# BSK3.net
KiCad netlist of a schematic drawn in EAGLE
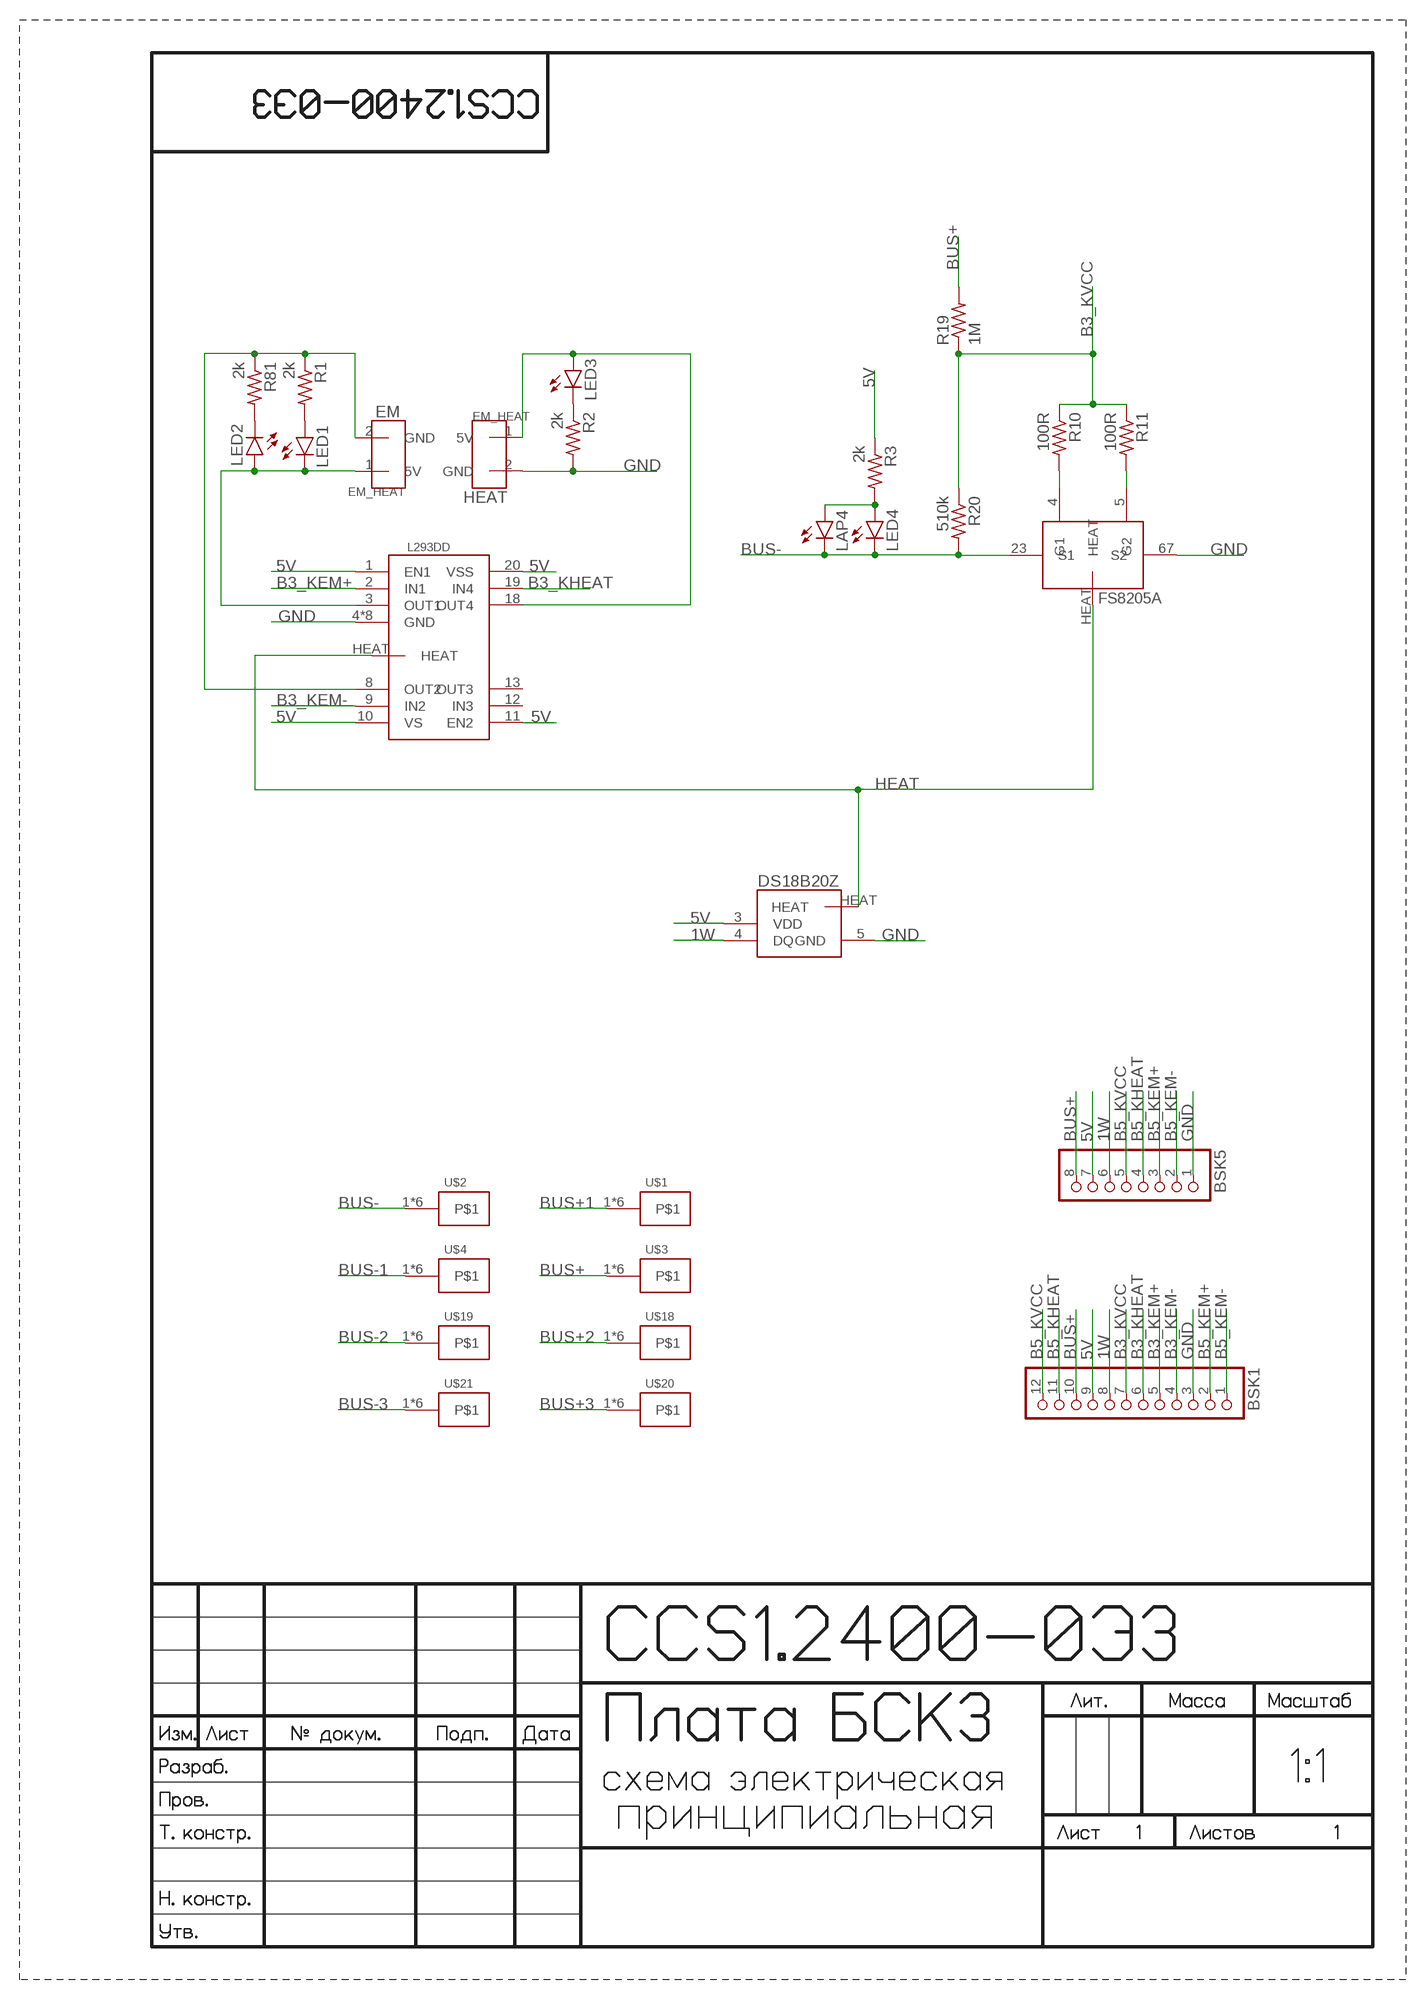
[diagram p0: schematic, sheet 1]

(export (version "E")
  (design (tool "Eeschema 10.0.6"))
  (components
    (comp (ref "BSK1")
      (value "PINHD-1X12")
      (footprint "eagle-import:1X12")
      (libsource (lib "eagle-import") (part "PINHD-1X12"))
    )
    (comp (ref "BSK5")
      (value "PINHD-1X8")
      (footprint "eagle-import:1X08")
      (libsource (lib "eagle-import") (part "PINHD-1X8"))
    )
    (comp (ref "DS18B20Z")
      (value "DS18B20Z")
      (footprint "eagle-import:DS18B20Z")
      (libsource (lib "eagle-import") (part "DS18B20Z"))
    )
    (comp (ref "FS8205A")
      (value "FS8205A+")
      (footprint "eagle-import:FS8205A+")
      (libsource (lib "eagle-import") (part "FS8205A+"))
    )
    (comp (ref "L293DD")
      (value "L293DD")
      (footprint "eagle-import:L293DD")
      (libsource (lib "eagle-import") (part "L293DD"))
    )
    (comp (ref "LAP4")
      (value "LAP4-BOTTOM")
      (footprint "eagle-import:P47F-BOTTOM")
      (libsource (lib "eagle-import") (part "P4-BOTTOMLA"))
    )
    (comp (ref "LED1")
      (value "LEDCHIPLED_0603")
      (footprint "eagle-import:CHIPLED_0603")
      (libsource (lib "eagle-import") (part "LEDCHIPLED_0603"))
    )
    (comp (ref "LED2")
      (value "LEDCHIPLED_0603")
      (footprint "eagle-import:CHIPLED_0603")
      (libsource (lib "eagle-import") (part "LEDCHIPLED_0603"))
    )
    (comp (ref "LED3")
      (value "LEDCHIPLED_0603")
      (footprint "eagle-import:CHIPLED_0603")
      (libsource (lib "eagle-import") (part "LEDCHIPLED_0603"))
    )
    (comp (ref "LED4")
      (value "LEDCHIPLED_0603")
      (footprint "eagle-import:CHIPLED_0603")
      (libsource (lib "eagle-import") (part "LEDCHIPLED_0603"))
    )
    (comp (ref "R1")
      (value "2k")
      (footprint "eagle-import:R0603")
      (libsource (lib "eagle-import") (part "R-US_R0603"))
    )
    (comp (ref "R2")
      (value "2k")
      (footprint "eagle-import:R0603")
      (libsource (lib "eagle-import") (part "R-US_R0603"))
    )
    (comp (ref "R3")
      (value "2k")
      (footprint "eagle-import:R0603")
      (libsource (lib "eagle-import") (part "R-US_R0603"))
    )
    (comp (ref "R10")
      (value "100R")
      (footprint "eagle-import:R0603")
      (libsource (lib "eagle-import") (part "R-US_R0603"))
    )
    (comp (ref "R11")
      (value "100R")
      (footprint "eagle-import:R0603")
      (libsource (lib "eagle-import") (part "R-US_R0603"))
    )
    (comp (ref "R19")
      (value "1M")
      (footprint "eagle-import:R0603")
      (libsource (lib "eagle-import") (part "R-US_R0603"))
    )
    (comp (ref "R20")
      (value "510k")
      (footprint "eagle-import:R0603")
      (libsource (lib "eagle-import") (part "R-US_R0603"))
    )
    (comp (ref "R81")
      (value "2k")
      (footprint "eagle-import:R0603")
      (libsource (lib "eagle-import") (part "R-US_R0603"))
    )
    (comp (ref "U$1")
      (value "KCONNECT")
      (footprint "eagle-import:KCONNECT")
      (libsource (lib "eagle-import") (part "KCONNECT"))
    )
    (comp (ref "U$2")
      (value "KCONNECT")
      (footprint "eagle-import:KCONNECT")
      (libsource (lib "eagle-import") (part "KCONNECT"))
    )
    (comp (ref "U$3")
      (value "KCONNECT")
      (footprint "eagle-import:KCONNECT")
      (libsource (lib "eagle-import") (part "KCONNECT"))
    )
    (comp (ref "U$4")
      (value "KCONNECT")
      (footprint "eagle-import:KCONNECT")
      (libsource (lib "eagle-import") (part "KCONNECT"))
    )
    (comp (ref "U$6")
      (value "EM_HEAT")
      (footprint "eagle-import:EM_HEAT")
      (libsource (lib "eagle-import") (part "EM_HEAT"))
    )
    (comp (ref "U$7")
      (value "EM_HEAT")
      (footprint "eagle-import:EM_HEAT")
      (libsource (lib "eagle-import") (part "EM_HEAT"))
    )
    (comp (ref "U$18")
      (value "KCONNECT")
      (footprint "eagle-import:KCONNECT")
      (libsource (lib "eagle-import") (part "KCONNECT"))
    )
    (comp (ref "U$19")
      (value "KCONNECT")
      (footprint "eagle-import:KCONNECT")
      (libsource (lib "eagle-import") (part "KCONNECT"))
    )
    (comp (ref "U$20")
      (value "KCONNECT")
      (footprint "eagle-import:KCONNECT")
      (libsource (lib "eagle-import") (part "KCONNECT"))
    )
    (comp (ref "U$21")
      (value "KCONNECT")
      (footprint "eagle-import:KCONNECT")
      (libsource (lib "eagle-import") (part "KCONNECT"))
    )
  )
  (nets
    (net (code "1") (name "/1W") (class "Default")
      (node (ref "BSK1") (pin "8") (pinfunction "8_8") (pintype "passive"))
      (node (ref "BSK5") (pin "6") (pinfunction "6_6") (pintype "passive"))
      (node (ref "DS18B20Z") (pin "4") (pinfunction "DQ_4") (pintype "bidirectional"))
    )
    (net (code "2") (name "/5V") (class "Default")
      (node (ref "BSK1") (pin "9") (pinfunction "9_9") (pintype "passive"))
      (node (ref "BSK5") (pin "7") (pinfunction "7_7") (pintype "passive"))
      (node (ref "DS18B20Z") (pin "3") (pinfunction "VDD_3") (pintype "bidirectional"))
      (node (ref "L293DD") (pin "1") (pinfunction "EN1_1") (pintype "bidirectional"))
      (node (ref "L293DD") (pin "10") (pinfunction "VS_10") (pintype "bidirectional"))
      (node (ref "L293DD") (pin "11") (pinfunction "EN2_11") (pintype "bidirectional"))
      (node (ref "L293DD") (pin "20") (pinfunction "VSS_20") (pintype "bidirectional"))
      (node (ref "R3") (pin "1") (pinfunction "1_1") (pintype "passive"))
    )
    (net (code "3") (name "/B3_KEM+") (class "Default")
      (node (ref "BSK1") (pin "5") (pinfunction "5_5") (pintype "passive"))
      (node (ref "L293DD") (pin "2") (pinfunction "IN1_2") (pintype "bidirectional"))
    )
    (net (code "4") (name "/B3_KEM-") (class "Default")
      (node (ref "BSK1") (pin "4") (pinfunction "4_4") (pintype "passive"))
      (node (ref "L293DD") (pin "9") (pinfunction "IN2_9") (pintype "bidirectional"))
    )
    (net (code "5") (name "/B3_KHEAT") (class "Default")
      (node (ref "BSK1") (pin "6") (pinfunction "6_6") (pintype "passive"))
      (node (ref "L293DD") (pin "19") (pinfunction "IN4_19") (pintype "bidirectional"))
    )
    (net (code "6") (name "/B3_KVCC") (class "Default")
      (node (ref "BSK1") (pin "7") (pinfunction "7_7") (pintype "passive"))
      (node (ref "R10") (pin "1") (pinfunction "1_1") (pintype "passive"))
      (node (ref "R11") (pin "1") (pinfunction "1_1") (pintype "passive"))
      (node (ref "R19") (pin "1") (pinfunction "1_1") (pintype "passive"))
      (node (ref "R20") (pin "1") (pinfunction "1_1") (pintype "passive"))
    )
    (net (code "7") (name "/B5_KEM+") (class "Default")
      (node (ref "BSK1") (pin "2") (pinfunction "2_2") (pintype "passive"))
      (node (ref "BSK5") (pin "3") (pinfunction "3_3") (pintype "passive"))
    )
    (net (code "8") (name "/B5_KEM-") (class "Default")
      (node (ref "BSK1") (pin "1") (pinfunction "1_1") (pintype "passive"))
      (node (ref "BSK5") (pin "2") (pinfunction "2_2") (pintype "passive"))
    )
    (net (code "9") (name "/B5_KHEAT") (class "Default")
      (node (ref "BSK1") (pin "11") (pinfunction "11_11") (pintype "passive"))
      (node (ref "BSK5") (pin "4") (pinfunction "4_4") (pintype "passive"))
    )
    (net (code "10") (name "/B5_KVCC") (class "Default")
      (node (ref "BSK1") (pin "12") (pinfunction "12_12") (pintype "passive"))
      (node (ref "BSK5") (pin "5") (pinfunction "5_5") (pintype "passive"))
    )
    (net (code "11") (name "/BUS+") (class "Default")
      (node (ref "BSK1") (pin "10") (pinfunction "10_10") (pintype "passive"))
      (node (ref "BSK5") (pin "8") (pinfunction "8_8") (pintype "passive"))
      (node (ref "R19") (pin "2") (pinfunction "2_2") (pintype "passive"))
      (node (ref "U$3") (pin "1") (pinfunction "P$1_1") (pintype "bidirectional"))
      (node (ref "U$3") (pin "2") (pinfunction "P$1_2") (pintype "bidirectional"))
      (node (ref "U$3") (pin "3") (pinfunction "P$1_3") (pintype "bidirectional"))
      (node (ref "U$3") (pin "4") (pinfunction "P$1_4") (pintype "bidirectional"))
      (node (ref "U$3") (pin "P$1") (pinfunction "P$1_P$1") (pintype "bidirectional"))
      (node (ref "U$3") (pin "P$2") (pinfunction "P$1_P$2") (pintype "bidirectional"))
    )
    (net (code "12") (name "/BUS+1") (class "Default")
      (node (ref "U$1") (pin "1") (pinfunction "P$1_1") (pintype "bidirectional"))
      (node (ref "U$1") (pin "2") (pinfunction "P$1_2") (pintype "bidirectional"))
      (node (ref "U$1") (pin "3") (pinfunction "P$1_3") (pintype "bidirectional"))
      (node (ref "U$1") (pin "4") (pinfunction "P$1_4") (pintype "bidirectional"))
      (node (ref "U$1") (pin "P$1") (pinfunction "P$1_P$1") (pintype "bidirectional"))
      (node (ref "U$1") (pin "P$2") (pinfunction "P$1_P$2") (pintype "bidirectional"))
    )
    (net (code "13") (name "/BUS+2") (class "Default")
      (node (ref "U$18") (pin "1") (pinfunction "P$1_1") (pintype "bidirectional"))
      (node (ref "U$18") (pin "2") (pinfunction "P$1_2") (pintype "bidirectional"))
      (node (ref "U$18") (pin "3") (pinfunction "P$1_3") (pintype "bidirectional"))
      (node (ref "U$18") (pin "4") (pinfunction "P$1_4") (pintype "bidirectional"))
      (node (ref "U$18") (pin "P$1") (pinfunction "P$1_P$1") (pintype "bidirectional"))
      (node (ref "U$18") (pin "P$2") (pinfunction "P$1_P$2") (pintype "bidirectional"))
    )
    (net (code "14") (name "/BUS+3") (class "Default")
      (node (ref "U$20") (pin "1") (pinfunction "P$1_1") (pintype "bidirectional"))
      (node (ref "U$20") (pin "2") (pinfunction "P$1_2") (pintype "bidirectional"))
      (node (ref "U$20") (pin "3") (pinfunction "P$1_3") (pintype "bidirectional"))
      (node (ref "U$20") (pin "4") (pinfunction "P$1_4") (pintype "bidirectional"))
      (node (ref "U$20") (pin "P$1") (pinfunction "P$1_P$1") (pintype "bidirectional"))
      (node (ref "U$20") (pin "P$2") (pinfunction "P$1_P$2") (pintype "bidirectional"))
    )
    (net (code "15") (name "/BUS-") (class "Default")
      (node (ref "FS8205A") (pin "23") (pinfunction "S1_23") (pintype "bidirectional"))
      (node (ref "LAP4") (pin "C") (pinfunction "C_C") (pintype "passive"))
      (node (ref "LED4") (pin "C") (pinfunction "C_C") (pintype "passive"))
      (node (ref "R20") (pin "2") (pinfunction "2_2") (pintype "passive"))
      (node (ref "U$2") (pin "1") (pinfunction "P$1_1") (pintype "bidirectional"))
      (node (ref "U$2") (pin "2") (pinfunction "P$1_2") (pintype "bidirectional"))
      (node (ref "U$2") (pin "3") (pinfunction "P$1_3") (pintype "bidirectional"))
      (node (ref "U$2") (pin "4") (pinfunction "P$1_4") (pintype "bidirectional"))
      (node (ref "U$2") (pin "P$1") (pinfunction "P$1_P$1") (pintype "bidirectional"))
      (node (ref "U$2") (pin "P$2") (pinfunction "P$1_P$2") (pintype "bidirectional"))
    )
    (net (code "16") (name "/BUS-1") (class "Default")
      (node (ref "U$4") (pin "1") (pinfunction "P$1_1") (pintype "bidirectional"))
      (node (ref "U$4") (pin "2") (pinfunction "P$1_2") (pintype "bidirectional"))
      (node (ref "U$4") (pin "3") (pinfunction "P$1_3") (pintype "bidirectional"))
      (node (ref "U$4") (pin "4") (pinfunction "P$1_4") (pintype "bidirectional"))
      (node (ref "U$4") (pin "P$1") (pinfunction "P$1_P$1") (pintype "bidirectional"))
      (node (ref "U$4") (pin "P$2") (pinfunction "P$1_P$2") (pintype "bidirectional"))
    )
    (net (code "17") (name "/BUS-2") (class "Default")
      (node (ref "U$19") (pin "1") (pinfunction "P$1_1") (pintype "bidirectional"))
      (node (ref "U$19") (pin "2") (pinfunction "P$1_2") (pintype "bidirectional"))
      (node (ref "U$19") (pin "3") (pinfunction "P$1_3") (pintype "bidirectional"))
      (node (ref "U$19") (pin "4") (pinfunction "P$1_4") (pintype "bidirectional"))
      (node (ref "U$19") (pin "P$1") (pinfunction "P$1_P$1") (pintype "bidirectional"))
      (node (ref "U$19") (pin "P$2") (pinfunction "P$1_P$2") (pintype "bidirectional"))
    )
    (net (code "18") (name "/BUS-3") (class "Default")
      (node (ref "U$21") (pin "1") (pinfunction "P$1_1") (pintype "bidirectional"))
      (node (ref "U$21") (pin "2") (pinfunction "P$1_2") (pintype "bidirectional"))
      (node (ref "U$21") (pin "3") (pinfunction "P$1_3") (pintype "bidirectional"))
      (node (ref "U$21") (pin "4") (pinfunction "P$1_4") (pintype "bidirectional"))
      (node (ref "U$21") (pin "P$1") (pinfunction "P$1_P$1") (pintype "bidirectional"))
      (node (ref "U$21") (pin "P$2") (pinfunction "P$1_P$2") (pintype "bidirectional"))
    )
    (net (code "19") (name "/GND") (class "Default")
      (node (ref "BSK1") (pin "3") (pinfunction "3_3") (pintype "passive"))
      (node (ref "BSK5") (pin "1") (pinfunction "1_1") (pintype "passive"))
      (node (ref "DS18B20Z") (pin "5") (pinfunction "GND_5") (pintype "bidirectional"))
      (node (ref "FS8205A") (pin "67") (pinfunction "S2_67") (pintype "bidirectional"))
      (node (ref "L293DD") (pin "14") (pinfunction "GND_14") (pintype "bidirectional"))
      (node (ref "L293DD") (pin "15") (pinfunction "GND_15") (pintype "bidirectional"))
      (node (ref "L293DD") (pin "16") (pinfunction "GND_16") (pintype "bidirectional"))
      (node (ref "L293DD") (pin "17") (pinfunction "GND_17") (pintype "bidirectional"))
      (node (ref "L293DD") (pin "4") (pinfunction "GND_4") (pintype "bidirectional"))
      (node (ref "L293DD") (pin "5") (pinfunction "GND_5") (pintype "bidirectional"))
      (node (ref "L293DD") (pin "6") (pinfunction "GND_6") (pintype "bidirectional"))
      (node (ref "L293DD") (pin "7") (pinfunction "GND_7") (pintype "bidirectional"))
      (node (ref "R2") (pin "2") (pinfunction "2_2") (pintype "passive"))
      (node (ref "U$7") (pin "2") (pinfunction "GND_2") (pintype "bidirectional"))
    )
    (net (code "20") (name "/HEAT") (class "Default")
      (node (ref "DS18B20Z") (pin "HEAT") (pinfunction "HEAT_HEAT") (pintype "bidirectional"))
      (node (ref "FS8205A") (pin "HEAT") (pinfunction "HEAT_HEAT") (pintype "bidirectional"))
      (node (ref "L293DD") (pin "HEAT") (pinfunction "HEAT_HEAT") (pintype "bidirectional"))
    )
    (net (code "21") (name "Net-(FS8205A-G1)") (class "Default")
      (node (ref "FS8205A") (pin "4") (pinfunction "G1_4") (pintype "bidirectional"))
      (node (ref "R10") (pin "2") (pinfunction "2_2") (pintype "passive"))
    )
    (net (code "22") (name "Net-(FS8205A-G2)") (class "Default")
      (node (ref "FS8205A") (pin "5") (pinfunction "G2_5") (pintype "bidirectional"))
      (node (ref "R11") (pin "2") (pinfunction "2_2") (pintype "passive"))
    )
    (net (code "23") (name "Net-(L293DD-OUT1)") (class "Default")
      (node (ref "L293DD") (pin "3") (pinfunction "OUT1_3") (pintype "bidirectional"))
      (node (ref "LED1") (pin "C") (pinfunction "C_C") (pintype "passive"))
      (node (ref "LED2") (pin "A") (pinfunction "A_A") (pintype "passive"))
      (node (ref "U$6") (pin "1") (pinfunction "5V_1") (pintype "bidirectional"))
    )
    (net (code "24") (name "Net-(L293DD-OUT2)") (class "Default")
      (node (ref "L293DD") (pin "8") (pinfunction "OUT2_8") (pintype "bidirectional"))
      (node (ref "R1") (pin "1") (pinfunction "1_1") (pintype "passive"))
      (node (ref "R81") (pin "1") (pinfunction "1_1") (pintype "passive"))
      (node (ref "U$6") (pin "2") (pinfunction "GND_2") (pintype "bidirectional"))
    )
    (net (code "25") (name "Net-(L293DD-OUT4)") (class "Default")
      (node (ref "L293DD") (pin "18") (pinfunction "OUT4_18") (pintype "bidirectional"))
      (node (ref "LED3") (pin "A") (pinfunction "A_A") (pintype "passive"))
      (node (ref "U$7") (pin "1") (pinfunction "5V_1") (pintype "bidirectional"))
    )
    (net (code "26") (name "Net-(LAP4-PadA)") (class "Default")
      (node (ref "LAP4") (pin "A") (pinfunction "A_A") (pintype "passive"))
      (node (ref "LED4") (pin "A") (pinfunction "A_A") (pintype "passive"))
      (node (ref "R3") (pin "2") (pinfunction "2_2") (pintype "passive"))
    )
    (net (code "27") (name "Net-(LED1-PadA)") (class "Default")
      (node (ref "LED1") (pin "A") (pinfunction "A_A") (pintype "passive"))
      (node (ref "R1") (pin "2") (pinfunction "2_2") (pintype "passive"))
    )
    (net (code "28") (name "Net-(LED2-PadC)") (class "Default")
      (node (ref "LED2") (pin "C") (pinfunction "C_C") (pintype "passive"))
      (node (ref "R81") (pin "2") (pinfunction "2_2") (pintype "passive"))
    )
    (net (code "29") (name "Net-(LED3-PadC)") (class "Default")
      (node (ref "LED3") (pin "C") (pinfunction "C_C") (pintype "passive"))
      (node (ref "R2") (pin "1") (pinfunction "1_1") (pintype "passive"))
    )
    (net (code "30") (name "unconnected-(L293DD-IN3-Pad12)") (class "Default")
      (node (ref "L293DD") (pin "12") (pinfunction "IN3_12") (pintype "bidirectional"))
    )
    (net (code "31") (name "unconnected-(L293DD-OUT3-Pad13)") (class "Default")
      (node (ref "L293DD") (pin "13") (pinfunction "OUT3_13") (pintype "bidirectional"))
    )
  )
)
